# HeaderBoard.net
KiCad netlist of a schematic drawn in Altium Designer
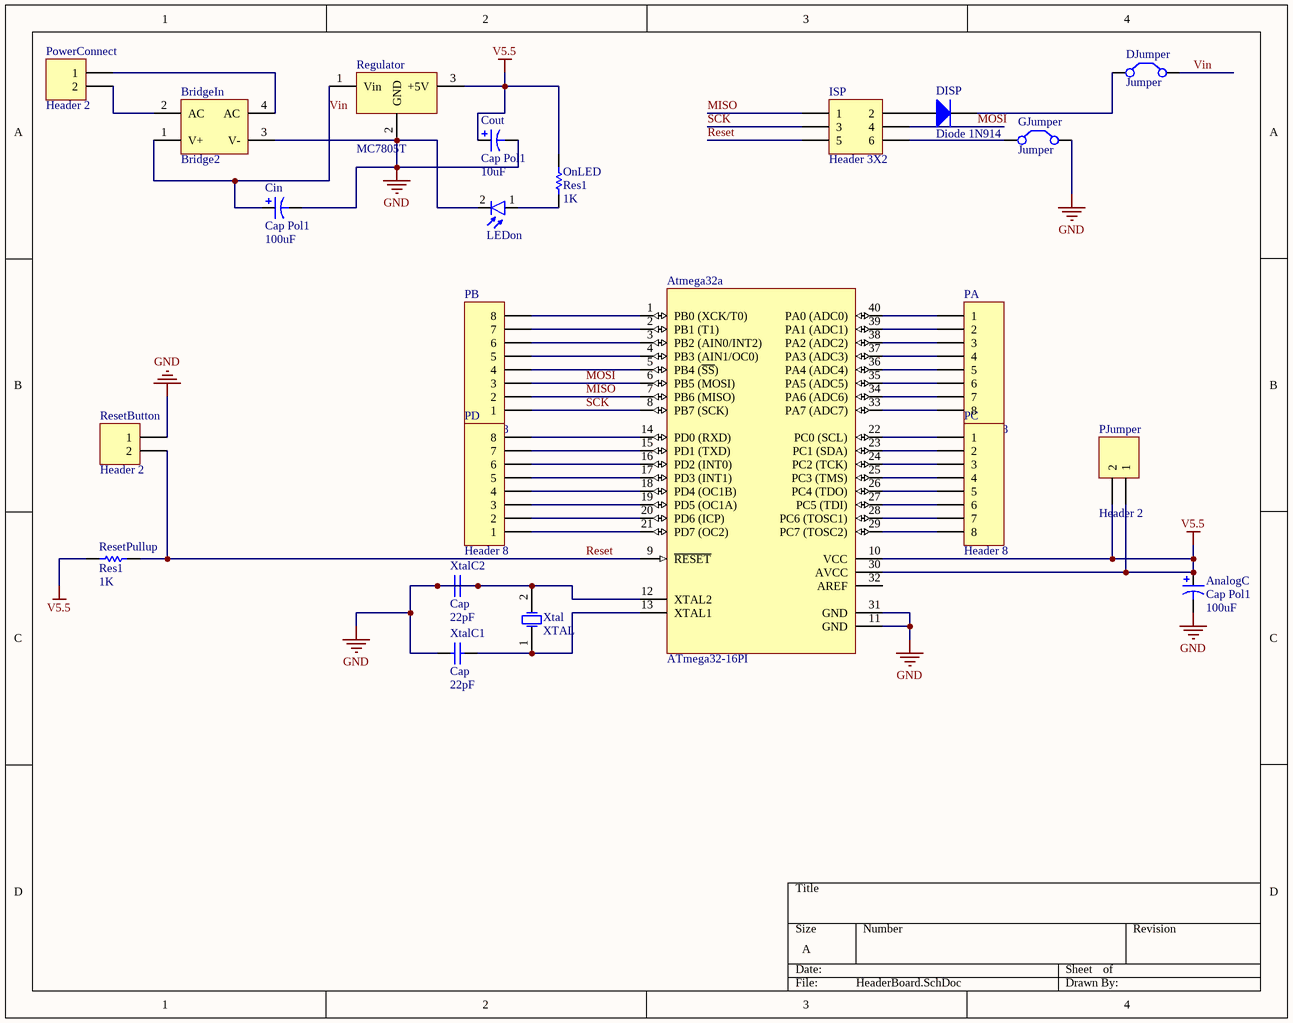
[diagram p0: HeaderBoard.SchDoc]

(export (version "E")
  (design (tool "Eeschema 10.0.6"))
  (components
    (comp (ref "AnalogC")
      (value "Cap Pol1")
      (footprint "cap 02")
      (description "Polarized Capacitor (Radial)")
      (fields (field (name "ALTIUM_VALUE") "100uF") (field (name "PUBLISHER") "Altium Limited"))
      (libsource (lib "") (part "Cap Pol1_1"))
    )
    (comp (ref "Atmega32a")
      (value "ATmega32-16PI")
      (footprint "40P6")
      (description "8-Bit AVR Microcontroller with 32K Bytes of In-System Programmable Flash Memory")
      (fields (field (name "PUBLISHER") "Altium Limited"))
      (libsource (lib "Atmel Microcontroller 8-Bit AVR") (part "ATmega32-16PI"))
    )
    (comp (ref "BridgeIn")
      (value "Bridge2")
      (footprint "Bridge")
      (description "Diode Bridge")
      (fields (field (name "PUBLISHER") "Altium Limited"))
      (libsource (lib "Miscellaneous Devices") (part "Bridge2"))
    )
    (comp (ref "Cin")
      (value "Cap Pol1")
      (footprint "cap 02")
      (description "Polarized Capacitor (Radial)")
      (fields (field (name "ALTIUM_VALUE") "100uF") (field (name "PUBLISHER") "Altium Limited"))
      (libsource (lib "Miscellaneous Devices") (part "Cap Pol1"))
    )
    (comp (ref "Cout")
      (value "Cap Pol1")
      (footprint "cap 02")
      (description "Polarized Capacitor (Radial)")
      (fields (field (name "ALTIUM_VALUE") "10uF") (field (name "PUBLISHER") "Altium Limited"))
      (libsource (lib "Miscellaneous Devices") (part "Cap Pol1"))
    )
    (comp (ref "DISP")
      (value "Diode 1N914")
      (footprint "DO-35")
      (description "High Conductance Fast Diode")
      (fields (field (name "PUBLISHER") "Altium Limited"))
      (libsource (lib "Miscellaneous Devices") (part "Diode 1N914"))
    )
    (comp (ref "DJumper")
      (value "Jumper")
      (footprint "RAD-0.2")
      (description "Jumper Wire")
      (fields (field (name "PUBLISHER") "Altium Limited"))
      (libsource (lib "Miscellaneous Devices") (part "Jumper"))
    )
    (comp (ref "GJumper")
      (value "Jumper")
      (footprint "RAD-0.2")
      (description "Jumper Wire")
      (fields (field (name "PUBLISHER") "Altium Limited"))
      (libsource (lib "Miscellaneous Devices") (part "Jumper"))
    )
    (comp (ref "ISP")
      (value "Header 3X2")
      (footprint "HDR2X3")
      (description "Header, 3-Pin, Dual row")
      (fields (field (name "PUBLISHER") "Altium Limited"))
      (libsource (lib "Miscellaneous Connectors") (part "Header 3X2"))
    )
    (comp (ref "LEDon")
      (value "IR Reciever")
      (footprint "LED-5mm-IR Reciver")
      (description "Infra Red Reciever Photo Diode")
      (fields (field (name "DESIGNER") "Saeid Jorablo"))
      (libsource (lib "My Library") (part "LED IR Reciever"))
    )
    (comp (ref "OnLED")
      (value "Res1")
      (footprint "AXIAL-0.3")
      (description "Resistor")
      (fields (field (name "ALTIUM_VALUE") "1K") (field (name "PUBLISHER") "Altium Limited"))
      (libsource (lib "Miscellaneous Devices") (part "Res1"))
    )
    (comp (ref "PA")
      (value "Header 8")
      (footprint "HDR1X8")
      (description "Header, 8-Pin")
      (fields (field (name "PUBLISHER") "Altium Limited"))
      (libsource (lib "Miscellaneous Connectors") (part "Header 8"))
    )
    (comp (ref "PB")
      (value "Header 8")
      (footprint "HDR1X8")
      (description "Header, 8-Pin")
      (fields (field (name "PUBLISHER") "Altium Limited"))
      (libsource (lib "") (part "Header 8_1"))
    )
    (comp (ref "PC")
      (value "Header 8")
      (footprint "HDR1X8")
      (description "Header, 8-Pin")
      (fields (field (name "PUBLISHER") "Altium Limited"))
      (libsource (lib "Miscellaneous Connectors") (part "Header 8"))
    )
    (comp (ref "PD")
      (value "Header 8")
      (footprint "HDR1X8")
      (description "Header, 8-Pin")
      (fields (field (name "PUBLISHER") "Altium Limited"))
      (libsource (lib "") (part "Header 8_1"))
    )
    (comp (ref "PJumper")
      (value "Header 2")
      (footprint "HDR1X2")
      (description "Header, 2-Pin")
      (fields (field (name "PUBLISHER") "Altium Limited"))
      (libsource (lib "") (part "Header 2_1"))
    )
    (comp (ref "PowerConnect")
      (value "Header 2")
      (footprint "HDR1X2")
      (description "Header, 2-Pin")
      (fields (field (name "PUBLISHER") "Altium Limited"))
      (libsource (lib "Miscellaneous Connectors") (part "Header 2"))
    )
    (comp (ref "Regulator")
      (value "MC7805T")
      (footprint "78XXCV - Right")
      (libsource (lib "Protel DOS Schematic") (part "MC7805T"))
    )
    (comp (ref "ResetButton")
      (value "Header 2")
      (footprint "HDR1X2")
      (description "Header, 2-Pin")
      (fields (field (name "PUBLISHER") "Altium Limited"))
      (libsource (lib "Miscellaneous Connectors") (part "Header 2"))
    )
    (comp (ref "ResetPullup")
      (value "Res1")
      (footprint "AXIAL-0.3")
      (description "Resistor")
      (fields (field (name "ALTIUM_VALUE") "1K") (field (name "PUBLISHER") "Altium Limited"))
      (libsource (lib "Miscellaneous Devices") (part "Res1"))
    )
    (comp (ref "Xtal")
      (value "XTAL")
      (footprint "Crystal SMD")
      (description "Crystal Oscillator")
      (fields (field (name "PUBLISHER") "Altium Limited"))
      (libsource (lib "Miscellaneous Devices") (part "XTAL"))
    )
    (comp (ref "XtalC1")
      (value "Cap")
      (footprint "Cap - 100nF")
      (description "Capacitor")
      (fields (field (name "ALTIUM_VALUE") "22pF") (field (name "PUBLISHER") "Altium Limited"))
      (libsource (lib "Miscellaneous Devices") (part "Cap"))
    )
    (comp (ref "XtalC2")
      (value "Cap")
      (footprint "Cap - 100nF")
      (description "Capacitor")
      (fields (field (name "ALTIUM_VALUE") "22pF") (field (name "PUBLISHER") "Altium Limited"))
      (libsource (lib "Miscellaneous Devices") (part "Cap"))
    )
  )
  (nets
    (net (code "1") (name "/MISO") (class "Default")
      (node (ref "Atmega32a") (pin "7") (pinfunction "PB6_(MISO)_7") (pintype "bidirectional"))
      (node (ref "ISP") (pin "1") (pinfunction "1_1") (pintype "passive"))
      (node (ref "PB") (pin "2") (pinfunction "2_2") (pintype "passive"))
    )
    (net (code "2") (name "/MOSI") (class "Default")
      (node (ref "Atmega32a") (pin "6") (pinfunction "PB5_(MOSI)_6") (pintype "bidirectional"))
      (node (ref "ISP") (pin "4") (pinfunction "4_4") (pintype "passive"))
      (node (ref "PB") (pin "3") (pinfunction "3_3") (pintype "passive"))
    )
    (net (code "3") (name "/Reset") (class "Default")
      (node (ref "Atmega32a") (pin "9") (pinfunction "~{RESET}_9") (pintype "input"))
      (node (ref "ISP") (pin "5") (pinfunction "5_5") (pintype "passive"))
      (node (ref "ResetButton") (pin "2") (pinfunction "2_2") (pintype "passive"))
      (node (ref "ResetPullup") (pin "2") (pinfunction "2_2") (pintype "passive"))
    )
    (net (code "4") (name "/SCK") (class "Default")
      (node (ref "Atmega32a") (pin "8") (pinfunction "PB7_(SCK)_8") (pintype "bidirectional"))
      (node (ref "ISP") (pin "3") (pinfunction "3_3") (pintype "passive"))
      (node (ref "PB") (pin "1") (pinfunction "1_1") (pintype "passive"))
    )
    (net (code "5") (name "/Vin") (class "Default")
      (node (ref "BridgeIn") (pin "1") (pinfunction "V+_1") (pintype "passive"))
      (node (ref "Cin") (pin "1") (pinfunction "1_1") (pintype "passive"))
      (node (ref "DJumper") (pin "2") (pinfunction "C2_2") (pintype "passive"))
      (node (ref "Regulator") (pin "1") (pinfunction "Vin_1") (pintype "passive"))
    )
    (net (code "6") (name "GND") (class "Default")
      (node (ref "AnalogC") (pin "2") (pinfunction "2_2") (pintype "passive"))
      (node (ref "Atmega32a") (pin "11") (pinfunction "GND_11") (pintype "power_in"))
      (node (ref "Atmega32a") (pin "12") (pinfunction "XTAL2_12") (pintype "passive"))
      (node (ref "Atmega32a") (pin "31") (pinfunction "GND_31") (pintype "power_in"))
      (node (ref "BridgeIn") (pin "3") (pinfunction "V-_3") (pintype "passive"))
      (node (ref "Cin") (pin "2") (pinfunction "2_2") (pintype "passive"))
      (node (ref "Cout") (pin "2") (pinfunction "2_2") (pintype "passive"))
      (node (ref "GJumper") (pin "2") (pinfunction "C2_2") (pintype "passive"))
      (node (ref "LEDon") (pin "2") (pinfunction "K_2") (pintype "passive"))
      (node (ref "Regulator") (pin "2") (pinfunction "GND_2") (pintype "passive"))
      (node (ref "ResetButton") (pin "1") (pinfunction "1_1") (pintype "passive"))
      (node (ref "Xtal") (pin "2") (pinfunction "OSC2_2") (pintype "passive"))
      (node (ref "XtalC1") (pin "1") (pinfunction "1_1") (pintype "passive"))
      (node (ref "XtalC2") (pin "1") (pinfunction "1_1") (pintype "passive"))
      (node (ref "XtalC2") (pin "2") (pinfunction "2_2") (pintype "passive"))
    )
    (net (code "7") (name "Net-(Atmega32a-PA0_(ADC0))") (class "Default")
      (node (ref "Atmega32a") (pin "40") (pinfunction "PA0_(ADC0)_40") (pintype "bidirectional"))
      (node (ref "PA") (pin "1") (pinfunction "1_1") (pintype "passive"))
    )
    (net (code "8") (name "Net-(Atmega32a-PA1_(ADC1))") (class "Default")
      (node (ref "Atmega32a") (pin "39") (pinfunction "PA1_(ADC1)_39") (pintype "bidirectional"))
      (node (ref "PA") (pin "2") (pinfunction "2_2") (pintype "passive"))
    )
    (net (code "9") (name "Net-(Atmega32a-PA2_(ADC2))") (class "Default")
      (node (ref "Atmega32a") (pin "38") (pinfunction "PA2_(ADC2)_38") (pintype "bidirectional"))
      (node (ref "PA") (pin "3") (pinfunction "3_3") (pintype "passive"))
    )
    (net (code "10") (name "Net-(Atmega32a-PA3_(ADC3))") (class "Default")
      (node (ref "Atmega32a") (pin "37") (pinfunction "PA3_(ADC3)_37") (pintype "bidirectional"))
      (node (ref "PA") (pin "4") (pinfunction "4_4") (pintype "passive"))
    )
    (net (code "11") (name "Net-(Atmega32a-PA4_(ADC4))") (class "Default")
      (node (ref "Atmega32a") (pin "36") (pinfunction "PA4_(ADC4)_36") (pintype "bidirectional"))
      (node (ref "PA") (pin "5") (pinfunction "5_5") (pintype "passive"))
    )
    (net (code "12") (name "Net-(Atmega32a-PA5_(ADC5))") (class "Default")
      (node (ref "Atmega32a") (pin "35") (pinfunction "PA5_(ADC5)_35") (pintype "bidirectional"))
      (node (ref "PA") (pin "6") (pinfunction "6_6") (pintype "passive"))
    )
    (net (code "13") (name "Net-(Atmega32a-PA6_(ADC6))") (class "Default")
      (node (ref "Atmega32a") (pin "34") (pinfunction "PA6_(ADC6)_34") (pintype "bidirectional"))
      (node (ref "PA") (pin "7") (pinfunction "7_7") (pintype "passive"))
    )
    (net (code "14") (name "Net-(Atmega32a-PA7_(ADC7))") (class "Default")
      (node (ref "Atmega32a") (pin "33") (pinfunction "PA7_(ADC7)_33") (pintype "bidirectional"))
      (node (ref "PA") (pin "8") (pinfunction "8_8") (pintype "passive"))
    )
    (net (code "15") (name "Net-(Atmega32a-PB0_(XCK{slash}T0))") (class "Default")
      (node (ref "Atmega32a") (pin "1") (pinfunction "PB0_(XCK/T0)_1") (pintype "bidirectional"))
      (node (ref "PB") (pin "8") (pinfunction "8_8") (pintype "passive"))
    )
    (net (code "16") (name "Net-(Atmega32a-PB1_(T1))") (class "Default")
      (node (ref "Atmega32a") (pin "2") (pinfunction "PB1_(T1)_2") (pintype "bidirectional"))
      (node (ref "PB") (pin "7") (pinfunction "7_7") (pintype "passive"))
    )
    (net (code "17") (name "Net-(Atmega32a-PB2_(AIN0{slash}INT2))") (class "Default")
      (node (ref "Atmega32a") (pin "3") (pinfunction "PB2_(AIN0/INT2)_3") (pintype "bidirectional"))
      (node (ref "PB") (pin "6") (pinfunction "6_6") (pintype "passive"))
    )
    (net (code "18") (name "Net-(Atmega32a-PB3_(AIN1{slash}OC0))") (class "Default")
      (node (ref "Atmega32a") (pin "4") (pinfunction "PB3_(AIN1/OC0)_4") (pintype "bidirectional"))
      (node (ref "PB") (pin "5") (pinfunction "5_5") (pintype "passive"))
    )
    (net (code "19") (name "Net-(Atmega32a-PB4_(~{SS}))") (class "Default")
      (node (ref "Atmega32a") (pin "5") (pinfunction "PB4_(~{SS})_5") (pintype "bidirectional"))
      (node (ref "PB") (pin "4") (pinfunction "4_4") (pintype "passive"))
    )
    (net (code "20") (name "Net-(Atmega32a-PC0_(SCL))") (class "Default")
      (node (ref "Atmega32a") (pin "22") (pinfunction "PC0_(SCL)_22") (pintype "bidirectional"))
      (node (ref "PC") (pin "1") (pinfunction "1_1") (pintype "passive"))
    )
    (net (code "21") (name "Net-(Atmega32a-PC1_(SDA))") (class "Default")
      (node (ref "Atmega32a") (pin "23") (pinfunction "PC1_(SDA)_23") (pintype "bidirectional"))
      (node (ref "PC") (pin "2") (pinfunction "2_2") (pintype "passive"))
    )
    (net (code "22") (name "Net-(Atmega32a-PC2_(TCK))") (class "Default")
      (node (ref "Atmega32a") (pin "24") (pinfunction "PC2_(TCK)_24") (pintype "bidirectional"))
      (node (ref "PC") (pin "3") (pinfunction "3_3") (pintype "passive"))
    )
    (net (code "23") (name "Net-(Atmega32a-PC3_(TMS))") (class "Default")
      (node (ref "Atmega32a") (pin "25") (pinfunction "PC3_(TMS)_25") (pintype "bidirectional"))
      (node (ref "PC") (pin "4") (pinfunction "4_4") (pintype "passive"))
    )
    (net (code "24") (name "Net-(Atmega32a-PC4_(TDO))") (class "Default")
      (node (ref "Atmega32a") (pin "26") (pinfunction "PC4_(TDO)_26") (pintype "bidirectional"))
      (node (ref "PC") (pin "5") (pinfunction "5_5") (pintype "passive"))
    )
    (net (code "25") (name "Net-(Atmega32a-PC5_(TDI))") (class "Default")
      (node (ref "Atmega32a") (pin "27") (pinfunction "PC5_(TDI)_27") (pintype "bidirectional"))
      (node (ref "PC") (pin "6") (pinfunction "6_6") (pintype "passive"))
    )
    (net (code "26") (name "Net-(Atmega32a-PC6_(TOSC1))") (class "Default")
      (node (ref "Atmega32a") (pin "28") (pinfunction "PC6_(TOSC1)_28") (pintype "bidirectional"))
      (node (ref "PC") (pin "7") (pinfunction "7_7") (pintype "passive"))
    )
    (net (code "27") (name "Net-(Atmega32a-PC7_(TOSC2))") (class "Default")
      (node (ref "Atmega32a") (pin "29") (pinfunction "PC7_(TOSC2)_29") (pintype "bidirectional"))
      (node (ref "PC") (pin "8") (pinfunction "8_8") (pintype "passive"))
    )
    (net (code "28") (name "Net-(Atmega32a-PD0_(RXD))") (class "Default")
      (node (ref "Atmega32a") (pin "14") (pinfunction "PD0_(RXD)_14") (pintype "bidirectional"))
      (node (ref "PD") (pin "8") (pinfunction "8_8") (pintype "passive"))
    )
    (net (code "29") (name "Net-(Atmega32a-PD1_(TXD))") (class "Default")
      (node (ref "Atmega32a") (pin "15") (pinfunction "PD1_(TXD)_15") (pintype "bidirectional"))
      (node (ref "PD") (pin "7") (pinfunction "7_7") (pintype "passive"))
    )
    (net (code "30") (name "Net-(Atmega32a-PD2_(INT0))") (class "Default")
      (node (ref "Atmega32a") (pin "16") (pinfunction "PD2_(INT0)_16") (pintype "bidirectional"))
      (node (ref "PD") (pin "6") (pinfunction "6_6") (pintype "passive"))
    )
    (net (code "31") (name "Net-(Atmega32a-PD3_(INT1))") (class "Default")
      (node (ref "Atmega32a") (pin "17") (pinfunction "PD3_(INT1)_17") (pintype "bidirectional"))
      (node (ref "PD") (pin "5") (pinfunction "5_5") (pintype "passive"))
    )
    (net (code "32") (name "Net-(Atmega32a-PD4_(OC1B))") (class "Default")
      (node (ref "Atmega32a") (pin "18") (pinfunction "PD4_(OC1B)_18") (pintype "bidirectional"))
      (node (ref "PD") (pin "4") (pinfunction "4_4") (pintype "passive"))
    )
    (net (code "33") (name "Net-(Atmega32a-PD5_(OC1A))") (class "Default")
      (node (ref "Atmega32a") (pin "19") (pinfunction "PD5_(OC1A)_19") (pintype "bidirectional"))
      (node (ref "PD") (pin "3") (pinfunction "3_3") (pintype "passive"))
    )
    (net (code "34") (name "Net-(Atmega32a-PD6_(ICP))") (class "Default")
      (node (ref "Atmega32a") (pin "20") (pinfunction "PD6_(ICP)_20") (pintype "bidirectional"))
      (node (ref "PD") (pin "2") (pinfunction "2_2") (pintype "passive"))
    )
    (net (code "35") (name "Net-(Atmega32a-PD7_(OC2))") (class "Default")
      (node (ref "Atmega32a") (pin "21") (pinfunction "PD7_(OC2)_21") (pintype "bidirectional"))
      (node (ref "PD") (pin "1") (pinfunction "1_1") (pintype "passive"))
    )
    (net (code "36") (name "Net-(Atmega32a-XTAL1)") (class "Default")
      (node (ref "Atmega32a") (pin "13") (pinfunction "XTAL1_13") (pintype "passive"))
      (node (ref "Xtal") (pin "1") (pinfunction "OSC1_1") (pintype "passive"))
      (node (ref "XtalC1") (pin "2") (pinfunction "2_2") (pintype "passive"))
    )
    (net (code "37") (name "Net-(BridgeIn-AC-Pad2)") (class "Default")
      (node (ref "BridgeIn") (pin "2") (pinfunction "AC_2") (pintype "passive"))
      (node (ref "PowerConnect") (pin "2") (pinfunction "2_2") (pintype "passive"))
    )
    (net (code "38") (name "Net-(BridgeIn-AC-Pad4)") (class "Default")
      (node (ref "BridgeIn") (pin "4") (pinfunction "AC_4") (pintype "passive"))
      (node (ref "PowerConnect") (pin "1") (pinfunction "1_1") (pintype "passive"))
    )
    (net (code "39") (name "Net-(DISP-A)") (class "Default")
      (node (ref "DISP") (pin "1") (pinfunction "A_1") (pintype "passive"))
      (node (ref "ISP") (pin "2") (pinfunction "2_2") (pintype "passive"))
    )
    (net (code "40") (name "Net-(DISP-K)") (class "Default")
      (node (ref "DISP") (pin "2") (pinfunction "K_2") (pintype "passive"))
      (node (ref "DJumper") (pin "1") (pinfunction "C1_1") (pintype "passive"))
    )
    (net (code "41") (name "Net-(GJumper-C1)") (class "Default")
      (node (ref "GJumper") (pin "1") (pinfunction "C1_1") (pintype "passive"))
      (node (ref "ISP") (pin "6") (pinfunction "6_6") (pintype "passive"))
    )
    (net (code "42") (name "Net-(LEDon-A)") (class "Default")
      (node (ref "LEDon") (pin "1") (pinfunction "A_1") (pintype "passive"))
      (node (ref "OnLED") (pin "1") (pinfunction "1_1") (pintype "passive"))
    )
    (net (code "43") (name "V5.5") (class "Default")
      (node (ref "AnalogC") (pin "1") (pinfunction "1_1") (pintype "passive"))
      (node (ref "Atmega32a") (pin "10") (pinfunction "VCC_10") (pintype "power_in"))
      (node (ref "Atmega32a") (pin "30") (pinfunction "AVCC_30") (pintype "power_in"))
      (node (ref "Cout") (pin "1") (pinfunction "1_1") (pintype "passive"))
      (node (ref "OnLED") (pin "2") (pinfunction "2_2") (pintype "passive"))
      (node (ref "PJumper") (pin "1") (pinfunction "1_1") (pintype "passive"))
      (node (ref "PJumper") (pin "2") (pinfunction "2_2") (pintype "passive"))
      (node (ref "Regulator") (pin "3") (pinfunction "+5V_3") (pintype "passive"))
      (node (ref "ResetPullup") (pin "1") (pinfunction "1_1") (pintype "passive"))
    )
    (net (code "44") (name "unconnected-(Atmega32a-AREF-Pad32)") (class "Default")
      (node (ref "Atmega32a") (pin "32") (pinfunction "AREF_32") (pintype "passive"))
    )
  )
)
